# cheapboard1_1.net
KiCad netlist of a schematic drawn in EAGLE
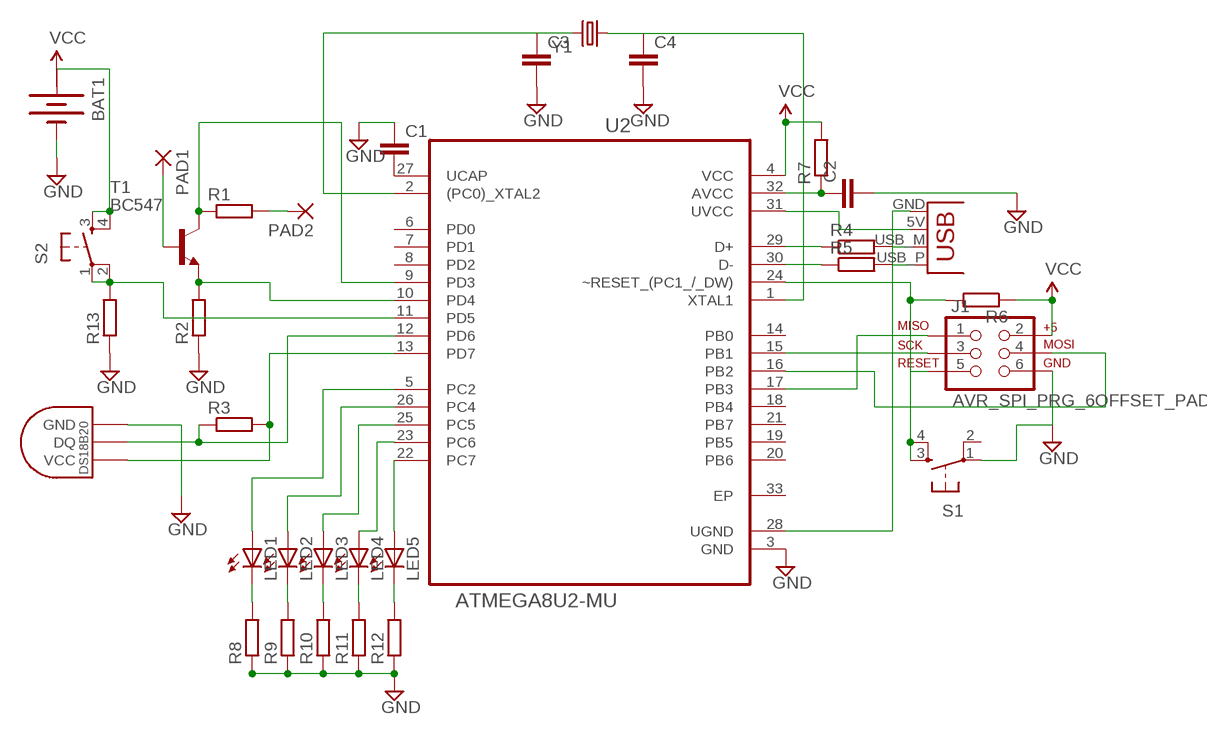
[diagram p0: schematic, sheet 1]

(export (version "E")
  (design (tool "Eeschema 10.0.6"))
  (components
    (comp (ref "BAT1")
      (value "BATTERY")
      (footprint "eagle-import:BATTERY")
      (libsource (lib "eagle-import") (part "BATTERY"))
    )
    (comp (ref "C1")
      (value "CAP0805")
      (footprint "eagle-import:0805")
      (libsource (lib "eagle-import") (part "CAP0805"))
    )
    (comp (ref "C2")
      (value "CAP0805")
      (footprint "eagle-import:0805")
      (libsource (lib "eagle-import") (part "CAP0805"))
    )
    (comp (ref "C3")
      (value "CAP0805")
      (footprint "eagle-import:0805")
      (libsource (lib "eagle-import") (part "CAP0805"))
    )
    (comp (ref "C4")
      (value "CAP0805")
      (footprint "eagle-import:0805")
      (libsource (lib "eagle-import") (part "CAP0805"))
    )
    (comp (ref "J1")
      (value "AVR_SPI_PRG_6OFFSET_PADS")
      (footprint "eagle-import:2X3_OFFSET")
      (libsource (lib "eagle-import") (part "AVR_SPI_PRG_6OFFSET_PADS"))
    )
    (comp (ref "JP1")
      (value "USBPCB")
      (footprint "eagle-import:USB-A-PCB")
      (libsource (lib "eagle-import") (part "USBPCB"))
    )
    (comp (ref "LED1")
      (value "LEDCHIPLED_0805")
      (footprint "eagle-import:CHIPLED_0805")
      (libsource (lib "eagle-import") (part "LEDCHIPLED_0805"))
    )
    (comp (ref "LED2")
      (value "LEDCHIPLED_0805")
      (footprint "eagle-import:CHIPLED_0805")
      (libsource (lib "eagle-import") (part "LEDCHIPLED_0805"))
    )
    (comp (ref "LED3")
      (value "LEDCHIPLED_0805")
      (footprint "eagle-import:CHIPLED_0805")
      (libsource (lib "eagle-import") (part "LEDCHIPLED_0805"))
    )
    (comp (ref "LED4")
      (value "LEDCHIPLED_0805")
      (footprint "eagle-import:CHIPLED_0805")
      (libsource (lib "eagle-import") (part "LEDCHIPLED_0805"))
    )
    (comp (ref "LED5")
      (value "LEDCHIPLED_0805")
      (footprint "eagle-import:CHIPLED_0805")
      (libsource (lib "eagle-import") (part "LEDCHIPLED_0805"))
    )
    (comp (ref "PAD1")
      (value "SMD5")
      (footprint "eagle-import:SMD2,54-5,08")
      (libsource (lib "eagle-import") (part "SMD5"))
    )
    (comp (ref "PAD2")
      (value "SMD5")
      (footprint "eagle-import:SMD2,54-5,08")
      (libsource (lib "eagle-import") (part "SMD5"))
    )
    (comp (ref "R1")
      (value "R-EU_M0805")
      (footprint "eagle-import:M0805")
      (libsource (lib "eagle-import") (part "R-EU_M0805"))
    )
    (comp (ref "R2")
      (value "R-EU_M0805")
      (footprint "eagle-import:M0805")
      (libsource (lib "eagle-import") (part "R-EU_M0805"))
    )
    (comp (ref "R3")
      (value "R-EU_M0805")
      (footprint "eagle-import:M0805")
      (libsource (lib "eagle-import") (part "R-EU_M0805"))
    )
    (comp (ref "R4")
      (value "R-EU_M0805")
      (footprint "eagle-import:M0805")
      (libsource (lib "eagle-import") (part "R-EU_M0805"))
    )
    (comp (ref "R5")
      (value "R-EU_M0805")
      (footprint "eagle-import:M0805")
      (libsource (lib "eagle-import") (part "R-EU_M0805"))
    )
    (comp (ref "R6")
      (value "R-EU_M0805")
      (footprint "eagle-import:M0805")
      (libsource (lib "eagle-import") (part "R-EU_M0805"))
    )
    (comp (ref "R7")
      (value "R-EU_M0805")
      (footprint "eagle-import:M0805")
      (libsource (lib "eagle-import") (part "R-EU_M0805"))
    )
    (comp (ref "R8")
      (value "R-EU_M0805")
      (footprint "eagle-import:M0805")
      (libsource (lib "eagle-import") (part "R-EU_M0805"))
    )
    (comp (ref "R9")
      (value "R-EU_M0805")
      (footprint "eagle-import:M0805")
      (libsource (lib "eagle-import") (part "R-EU_M0805"))
    )
    (comp (ref "R10")
      (value "R-EU_M0805")
      (footprint "eagle-import:M0805")
      (libsource (lib "eagle-import") (part "R-EU_M0805"))
    )
    (comp (ref "R11")
      (value "R-EU_M0805")
      (footprint "eagle-import:M0805")
      (libsource (lib "eagle-import") (part "R-EU_M0805"))
    )
    (comp (ref "R12")
      (value "R-EU_M0805")
      (footprint "eagle-import:M0805")
      (libsource (lib "eagle-import") (part "R-EU_M0805"))
    )
    (comp (ref "R13")
      (value "R-EU_M0805")
      (footprint "eagle-import:M0805")
      (libsource (lib "eagle-import") (part "R-EU_M0805"))
    )
    (comp (ref "S1")
      (value "TAC_SWITCHSMD")
      (footprint "eagle-import:TACTILE_SWITCH_SMD")
      (libsource (lib "eagle-import") (part "TAC_SWITCHSMD"))
    )
    (comp (ref "S2")
      (value "TAC_SWITCHSMD")
      (footprint "eagle-import:TACTILE_SWITCH_SMD")
      (libsource (lib "eagle-import") (part "TAC_SWITCHSMD"))
    )
    (comp (ref "T1")
      (value "BC547")
      (footprint "eagle-import:TO92")
      (libsource (lib "eagle-import") (part "BC547"))
    )
    (comp (ref "U$1")
      (value "DS1820SOIC")
      (footprint "eagle-import:DS18B20_SOIC")
      (libsource (lib "eagle-import") (part "DS1820SOIC"))
    )
    (comp (ref "U2")
      (value "ATMEGA8U2-MU")
      (footprint "eagle-import:QFN50P500X500X100-33N")
      (libsource (lib "eagle-import") (part "ATMEGA8U2-MU"))
    )
    (comp (ref "Y1")
      (value "CRYSTAL5X3")
      (footprint "eagle-import:CRYSTAL-SMD-5X3")
      (libsource (lib "eagle-import") (part "CRYSTAL5X3"))
    )
  )
  (nets
    (net (code "1") (name "/+") (class "Default")
      (node (ref "BAT1") (pin "+@1") (pinfunction "+_+@1") (pintype "power_in"))
    )
    (net (code "2") (name "GND") (class "Default")
      (node (ref "BAT1") (pin "-") (pinfunction "-_-") (pintype "power_in"))
      (node (ref "C1") (pin "1") (pinfunction "1_1") (pintype "passive"))
      (node (ref "C2") (pin "2") (pinfunction "2_2") (pintype "passive"))
      (node (ref "C3") (pin "2") (pinfunction "2_2") (pintype "passive"))
      (node (ref "C4") (pin "2") (pinfunction "2_2") (pintype "passive"))
      (node (ref "J1") (pin "6") (pinfunction "6_6") (pintype "passive"))
      (node (ref "R10") (pin "1") (pinfunction "1_1") (pintype "passive"))
      (node (ref "R11") (pin "1") (pinfunction "1_1") (pintype "passive"))
      (node (ref "R12") (pin "1") (pinfunction "1_1") (pintype "passive"))
      (node (ref "R13") (pin "1") (pinfunction "1_1") (pintype "passive"))
      (node (ref "R2") (pin "1") (pinfunction "1_1") (pintype "passive"))
      (node (ref "R8") (pin "1") (pinfunction "1_1") (pintype "passive"))
      (node (ref "R9") (pin "1") (pinfunction "1_1") (pintype "passive"))
      (node (ref "S1") (pin "1") (pinfunction "1_1") (pintype "passive"))
      (node (ref "U$1") (pin "GND") (pinfunction "GND_GND") (pintype "power_in"))
      (node (ref "U2") (pin "3") (pinfunction "GND_3") (pintype "passive"))
    )
    (net (code "3") (name "Net-(JP1-D+)") (class "Default")
      (node (ref "JP1") (pin "USB_P") (pinfunction "D+_USB_P") (pintype "bidirectional"))
      (node (ref "R5") (pin "2") (pinfunction "2_2") (pintype "passive"))
    )
    (net (code "4") (name "Net-(JP1-D-)") (class "Default")
      (node (ref "JP1") (pin "USB_M") (pinfunction "D-_USB_M") (pintype "bidirectional"))
      (node (ref "R4") (pin "2") (pinfunction "2_2") (pintype "passive"))
    )
    (net (code "5") (name "Net-(JP1-VBUS)") (class "Default")
      (node (ref "JP1") (pin "5V") (pinfunction "VBUS_5V") (pintype "bidirectional"))
      (node (ref "U2") (pin "31") (pinfunction "UVCC_31") (pintype "power_in"))
    )
    (net (code "6") (name "Net-(LED1-PadC)") (class "Default")
      (node (ref "LED1") (pin "C") (pinfunction "C_C") (pintype "passive"))
      (node (ref "R8") (pin "2") (pinfunction "2_2") (pintype "passive"))
    )
    (net (code "7") (name "Net-(LED2-PadC)") (class "Default")
      (node (ref "LED2") (pin "C") (pinfunction "C_C") (pintype "passive"))
      (node (ref "R9") (pin "2") (pinfunction "2_2") (pintype "passive"))
    )
    (net (code "8") (name "Net-(LED3-PadC)") (class "Default")
      (node (ref "LED3") (pin "C") (pinfunction "C_C") (pintype "passive"))
      (node (ref "R10") (pin "2") (pinfunction "2_2") (pintype "passive"))
    )
    (net (code "9") (name "Net-(LED4-PadC)") (class "Default")
      (node (ref "LED4") (pin "C") (pinfunction "C_C") (pintype "passive"))
      (node (ref "R11") (pin "2") (pinfunction "2_2") (pintype "passive"))
    )
    (net (code "10") (name "Net-(LED5-PadC)") (class "Default")
      (node (ref "LED5") (pin "C") (pinfunction "C_C") (pintype "passive"))
      (node (ref "R12") (pin "2") (pinfunction "2_2") (pintype "passive"))
    )
    (net (code "11") (name "Net-(PAD1-P)") (class "Default")
      (node (ref "PAD1") (pin "1") (pinfunction "P_1") (pintype "passive"))
      (node (ref "T1") (pin "2") (pinfunction "B_2") (pintype "passive"))
    )
    (net (code "12") (name "Net-(PAD2-P)") (class "Default")
      (node (ref "PAD2") (pin "1") (pinfunction "P_1") (pintype "passive"))
      (node (ref "R1") (pin "2") (pinfunction "2_2") (pintype "passive"))
    )
    (net (code "13") (name "Net-(T1-C)") (class "Default")
      (node (ref "R1") (pin "1") (pinfunction "1_1") (pintype "passive"))
      (node (ref "T1") (pin "3") (pinfunction "C_3") (pintype "passive"))
      (node (ref "U2") (pin "9") (pinfunction "PD3_9") (pintype "bidirectional"))
    )
    (net (code "14") (name "Net-(T1-E)") (class "Default")
      (node (ref "R2") (pin "2") (pinfunction "2_2") (pintype "passive"))
      (node (ref "T1") (pin "1") (pinfunction "E_1") (pintype "passive"))
      (node (ref "U2") (pin "10") (pinfunction "PD4_10") (pintype "bidirectional"))
    )
    (net (code "15") (name "Net-(U2-(PC0)_XTAL2)") (class "Default")
      (node (ref "C3") (pin "1") (pinfunction "1_1") (pintype "passive"))
      (node (ref "U2") (pin "2") (pinfunction "(PC0)_XTAL2_2") (pintype "bidirectional"))
      (node (ref "Y1") (pin "3") (pinfunction "2_3") (pintype "passive"))
    )
    (net (code "16") (name "Net-(U2-AVCC)") (class "Default")
      (node (ref "C2") (pin "1") (pinfunction "1_1") (pintype "passive"))
      (node (ref "R7") (pin "1") (pinfunction "1_1") (pintype "passive"))
      (node (ref "U2") (pin "32") (pinfunction "AVCC_32") (pintype "power_in"))
    )
    (net (code "17") (name "Net-(U2-D+)") (class "Default")
      (node (ref "R4") (pin "1") (pinfunction "1_1") (pintype "passive"))
      (node (ref "U2") (pin "29") (pinfunction "D+_29") (pintype "passive"))
    )
    (net (code "18") (name "Net-(U2-D-)") (class "Default")
      (node (ref "R5") (pin "1") (pinfunction "1_1") (pintype "passive"))
      (node (ref "U2") (pin "30") (pinfunction "D-_30") (pintype "passive"))
    )
    (net (code "19") (name "Net-(U2-PB1)") (class "Default")
      (node (ref "J1") (pin "3") (pinfunction "3_3") (pintype "passive"))
      (node (ref "U2") (pin "15") (pinfunction "PB1_15") (pintype "bidirectional"))
    )
    (net (code "20") (name "Net-(U2-PB2)") (class "Default")
      (node (ref "J1") (pin "4") (pinfunction "4_4") (pintype "passive"))
      (node (ref "U2") (pin "16") (pinfunction "PB2_16") (pintype "bidirectional"))
    )
    (net (code "21") (name "Net-(U2-PB3)") (class "Default")
      (node (ref "J1") (pin "1") (pinfunction "1_1") (pintype "passive"))
      (node (ref "U2") (pin "17") (pinfunction "PB3_17") (pintype "bidirectional"))
    )
    (net (code "22") (name "Net-(U2-PC2)") (class "Default")
      (node (ref "LED1") (pin "A") (pinfunction "A_A") (pintype "passive"))
      (node (ref "U2") (pin "5") (pinfunction "PC2_5") (pintype "bidirectional"))
    )
    (net (code "23") (name "Net-(U2-PC4)") (class "Default")
      (node (ref "LED2") (pin "A") (pinfunction "A_A") (pintype "passive"))
      (node (ref "U2") (pin "26") (pinfunction "PC4_26") (pintype "bidirectional"))
    )
    (net (code "24") (name "Net-(U2-PC5)") (class "Default")
      (node (ref "LED3") (pin "A") (pinfunction "A_A") (pintype "passive"))
      (node (ref "U2") (pin "25") (pinfunction "PC5_25") (pintype "bidirectional"))
    )
    (net (code "25") (name "Net-(U2-PC6)") (class "Default")
      (node (ref "LED4") (pin "A") (pinfunction "A_A") (pintype "passive"))
      (node (ref "U2") (pin "23") (pinfunction "PC6_23") (pintype "bidirectional"))
    )
    (net (code "26") (name "Net-(U2-PC7)") (class "Default")
      (node (ref "LED5") (pin "A") (pinfunction "A_A") (pintype "passive"))
      (node (ref "U2") (pin "22") (pinfunction "PC7_22") (pintype "bidirectional"))
    )
    (net (code "27") (name "Net-(U2-PD5)") (class "Default")
      (node (ref "R13") (pin "2") (pinfunction "2_2") (pintype "passive"))
      (node (ref "S2") (pin "1") (pinfunction "1_1") (pintype "passive"))
      (node (ref "S2") (pin "2") (pinfunction "2_2") (pintype "passive"))
      (node (ref "U2") (pin "11") (pinfunction "PD5_11") (pintype "bidirectional"))
    )
    (net (code "28") (name "Net-(U2-PD6)") (class "Default")
      (node (ref "R3") (pin "1") (pinfunction "1_1") (pintype "passive"))
      (node (ref "U$1") (pin "DQ") (pinfunction "DQ_DQ") (pintype "bidirectional"))
      (node (ref "U2") (pin "12") (pinfunction "PD6_12") (pintype "bidirectional"))
    )
    (net (code "29") (name "Net-(U2-PD7)") (class "Default")
      (node (ref "R3") (pin "2") (pinfunction "2_2") (pintype "passive"))
      (node (ref "U$1") (pin "VCC") (pinfunction "VCC_VCC") (pintype "power_in"))
      (node (ref "U2") (pin "13") (pinfunction "PD7_13") (pintype "bidirectional"))
    )
    (net (code "30") (name "Net-(U2-UCAP)") (class "Default")
      (node (ref "C1") (pin "2") (pinfunction "2_2") (pintype "passive"))
      (node (ref "U2") (pin "27") (pinfunction "UCAP_27") (pintype "power_in"))
    )
    (net (code "31") (name "Net-(U2-UGND)") (class "Default")
      (node (ref "JP1") (pin "GND") (pinfunction "GND_GND") (pintype "bidirectional"))
      (node (ref "U2") (pin "28") (pinfunction "UGND_28") (pintype "passive"))
    )
    (net (code "32") (name "Net-(U2-XTAL1)") (class "Default")
      (node (ref "C4") (pin "1") (pinfunction "1_1") (pintype "passive"))
      (node (ref "U2") (pin "1") (pinfunction "XTAL1_1") (pintype "input"))
      (node (ref "Y1") (pin "1") (pinfunction "1_1") (pintype "passive"))
    )
    (net (code "33") (name "Net-(U2-~{RESET_(PC1_{slash}_DW}))") (class "Default")
      (node (ref "J1") (pin "5") (pinfunction "5_5") (pintype "passive"))
      (node (ref "R6") (pin "2") (pinfunction "2_2") (pintype "passive"))
      (node (ref "S1") (pin "3") (pinfunction "3_3") (pintype "passive"))
      (node (ref "S1") (pin "4") (pinfunction "4_4") (pintype "passive"))
      (node (ref "U2") (pin "24") (pinfunction "~{RESET_(PC1_/_DW})_24") (pintype "bidirectional"))
    )
    (net (code "34") (name "VCC") (class "Default")
      (node (ref "BAT1") (pin "+") (pinfunction "+_+") (pintype "power_in"))
      (node (ref "J1") (pin "2") (pinfunction "2_2") (pintype "passive"))
      (node (ref "R6") (pin "1") (pinfunction "1_1") (pintype "passive"))
      (node (ref "R7") (pin "2") (pinfunction "2_2") (pintype "passive"))
      (node (ref "S2") (pin "3") (pinfunction "3_3") (pintype "passive"))
      (node (ref "S2") (pin "4") (pinfunction "4_4") (pintype "passive"))
      (node (ref "U2") (pin "4") (pinfunction "VCC_4") (pintype "power_in"))
    )
    (net (code "35") (name "unconnected-(S1-Pad2)") (class "Default")
      (node (ref "S1") (pin "2") (pinfunction "2_2") (pintype "passive"))
    )
    (net (code "36") (name "unconnected-(U2-EP-Pad33)") (class "Default")
      (node (ref "U2") (pin "33") (pinfunction "EP_33") (pintype "passive"))
    )
    (net (code "37") (name "unconnected-(U2-PB0-Pad14)") (class "Default")
      (node (ref "U2") (pin "14") (pinfunction "PB0_14") (pintype "bidirectional"))
    )
    (net (code "38") (name "unconnected-(U2-PB4-Pad18)") (class "Default")
      (node (ref "U2") (pin "18") (pinfunction "PB4_18") (pintype "bidirectional"))
    )
    (net (code "39") (name "unconnected-(U2-PB5-Pad19)") (class "Default")
      (node (ref "U2") (pin "19") (pinfunction "PB5_19") (pintype "bidirectional"))
    )
    (net (code "40") (name "unconnected-(U2-PB6-Pad20)") (class "Default")
      (node (ref "U2") (pin "20") (pinfunction "PB6_20") (pintype "bidirectional"))
    )
    (net (code "41") (name "unconnected-(U2-PB7-Pad21)") (class "Default")
      (node (ref "U2") (pin "21") (pinfunction "PB7_21") (pintype "bidirectional"))
    )
    (net (code "42") (name "unconnected-(U2-PD0-Pad6)") (class "Default")
      (node (ref "U2") (pin "6") (pinfunction "PD0_6") (pintype "bidirectional"))
    )
    (net (code "43") (name "unconnected-(U2-PD1-Pad7)") (class "Default")
      (node (ref "U2") (pin "7") (pinfunction "PD1_7") (pintype "bidirectional"))
    )
    (net (code "44") (name "unconnected-(U2-PD2-Pad8)") (class "Default")
      (node (ref "U2") (pin "8") (pinfunction "PD2_8") (pintype "bidirectional"))
    )
  )
)
